# Drive_Module.net
KiCad netlist of a schematic drawn in Altium Designer
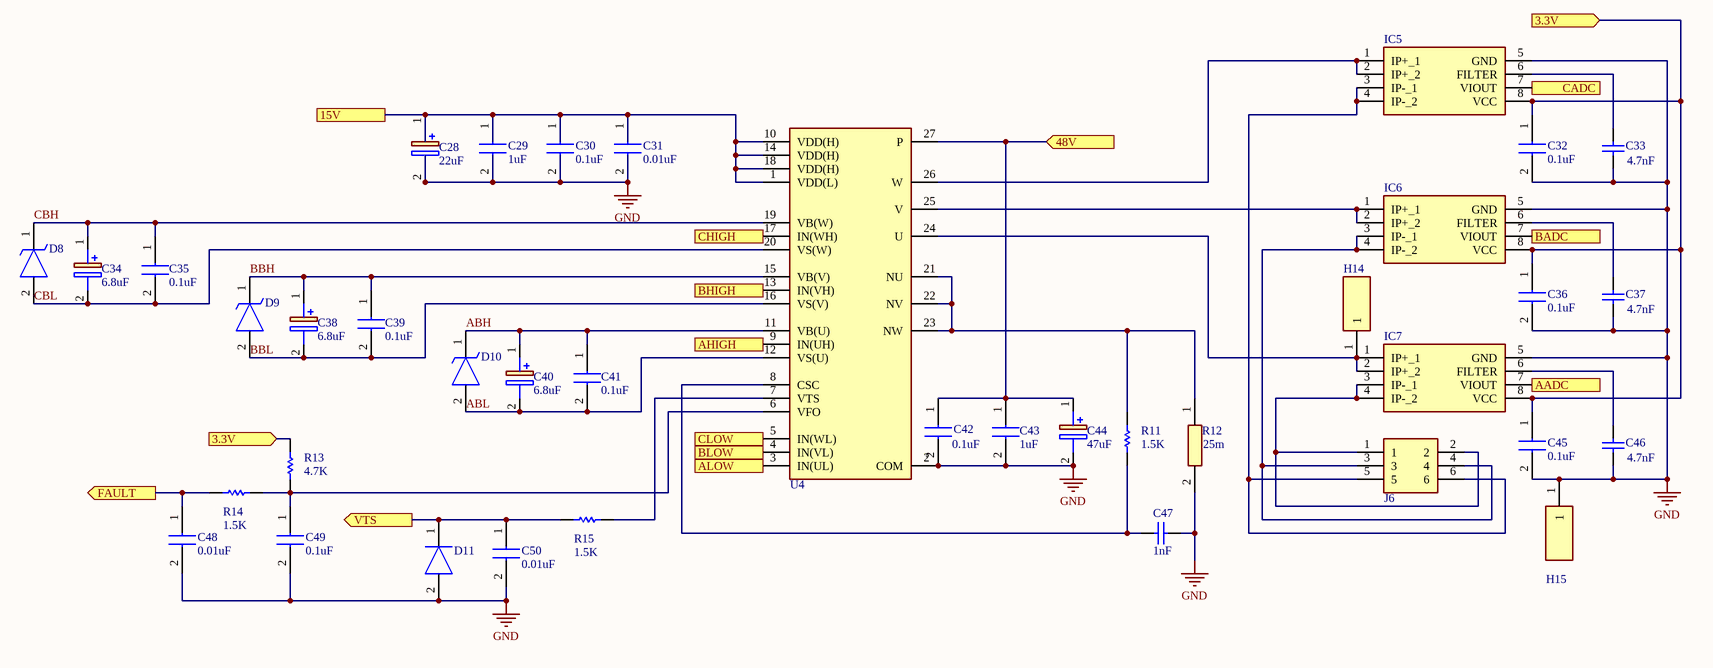
[diagram p0: Drive_Module.SchDoc]

(export (version "E")
  (design (tool "Eeschema 10.0.6"))
  (components
    (comp (ref "C28")
      (value "22uF")
      (footprint "CAPPRD200W50D550H1250")
      (description "Capacitor Polarised  25V")
      (fields
        (field (name "MANUFACTURER_PART_NUMBER") "UPW1E220MDD")
        (field (name "MOUSER PART NUMBER") "647-UPW1E220MDD")
      )
      (libsource (lib "ee_453_Schulz") (part "UPW1E220MDD"))
    )
    (comp (ref "C29")
      (value "1uF")
      (footprint "C330C105K5R5TA")
      (description "Capacitor 50V")
      (fields
        (field (name "MANUFACTURER_PART_NUMBER") "C330C105K5R5TA")
        (field (name "MOUSER PART NUMBER") "80-C330C105K5R")
      )
      (libsource (lib "ee_453_Schulz") (part "C330C105K5R5TA"))
    )
    (comp (ref "C30")
      (value "0.1uF")
      (footprint "K104K10X7RF5UH5")
      (description "Capacitor 50V")
      (fields
        (field (name "MANUFACTURER_PART_NUMBER") "K104K10X7RF5UH5")
        (field (name "MOUSER PART NUMBER") "594-K104K10X7RF5UH5")
      )
      (libsource (lib "ee_453_Schulz") (part "K104K10X7RF5UH5"))
    )
    (comp (ref "C31")
      (value "0.01uF")
      (footprint "C315C103K5R5TA7990")
      (description "Capacitor 50V")
      (fields (field (name "MANUFACTURER_PART_NUMBER") "C315C103K5R5TA7990"))
      (libsource (lib "ee_453_Schulz") (part "C315C103K5R5TA7990"))
    )
    (comp (ref "C32")
      (value "0.1uF")
      (footprint "CAPC1608X95N")
      (description "Capacitor 50V")
      (fields
        (field (name "MANUFACTURER_PART_NUMBER") "C0603C104K5RAC3121")
        (field (name "MOUSER PART NUMBER") "80-C603C104K5RAC3121")
      )
      (libsource (lib "ee_453_Schulz") (part "C0603C104K5RAC3121"))
    )
    (comp (ref "C33")
      (value "4.7nF")
      (footprint "CAPC1608X90X35ML10T15")
      (fields (field (name "PART NUMBER") "GRM188R71H472KA01D") (field (name "MANUFACTURER") "Murata"))
      (libsource (lib "Altium Content Vault") (part "CAP"))
    )
    (comp (ref "C34")
      (value "6.8uF")
      (footprint "CAPPRD150W45D425H1250")
      (description "Capacitor Polarised")
      (fields
        (field (name "MANUFACTURER_PART_NUMBER") "UPW1J6R8MDD6")
        (field (name "RS PART NUMBER") "8515424")
      )
      (libsource (lib "ee_453_Schulz") (part "UPW1J6R8MDD6"))
    )
    (comp (ref "C35")
      (value "0.1uF")
      (footprint "K104K10X7RF5UH5")
      (description "Capacitor 50V")
      (fields
        (field (name "MANUFACTURER_PART_NUMBER") "K104K10X7RF5UH5")
        (field (name "MOUSER PART NUMBER") "594-K104K10X7RF5UH5")
      )
      (libsource (lib "ee_453_Schulz") (part "K104K10X7RF5UH5"))
    )
    (comp (ref "C36")
      (value "0.1uF")
      (footprint "CAPC1608X95N")
      (description "Capacitor 50V")
      (fields
        (field (name "MANUFACTURER_PART_NUMBER") "C0603C104K5RAC3121")
        (field (name "MOUSER PART NUMBER") "80-C603C104K5RAC3121")
      )
      (libsource (lib "ee_453_Schulz") (part "C0603C104K5RAC3121"))
    )
    (comp (ref "C37")
      (value "4.7nF")
      (footprint "CAPC1608X90X35ML10T15")
      (fields (field (name "PART NUMBER") "GRM188R71H472KA01D") (field (name "MANUFACTURER") "Murata"))
      (libsource (lib "Altium Content Vault") (part "CAP"))
    )
    (comp (ref "C38")
      (value "6.8uF")
      (footprint "CAPPRD150W45D425H1250")
      (description "Capacitor Polarised")
      (fields
        (field (name "MANUFACTURER_PART_NUMBER") "UPW1J6R8MDD6")
        (field (name "RS PART NUMBER") "8515424")
      )
      (libsource (lib "ee_453_Schulz") (part "UPW1J6R8MDD6"))
    )
    (comp (ref "C39")
      (value "0.1uF")
      (footprint "K104K10X7RF5UH5")
      (description "Capacitor 50V")
      (fields
        (field (name "MANUFACTURER_PART_NUMBER") "K104K10X7RF5UH5")
        (field (name "MOUSER PART NUMBER") "594-K104K10X7RF5UH5")
      )
      (libsource (lib "ee_453_Schulz") (part "K104K10X7RF5UH5"))
    )
    (comp (ref "C40")
      (value "6.8uF")
      (footprint "CAPPRD150W45D425H1250")
      (description "UPW1J6R8MDD6")
      (fields (field (name "RS PART NUMBER") "8515424"))
      (libsource (lib "ee_453_Schulz") (part "UPW1J6R8MDD6"))
    )
    (comp (ref "C41")
      (value "0.1uF")
      (footprint "K104K10X7RF5UH5")
      (description "Capacitor 50V")
      (fields
        (field (name "MANUFACTURER_PART_NUMBER") "K104K10X7RF5UH5")
        (field (name "MOUSER PART NUMBER") "594-K104K10X7RF5UH5")
      )
      (libsource (lib "ee_453_Schulz") (part "K104K10X7RF5UH5"))
    )
    (comp (ref "C42")
      (value "0.1uF")
      (footprint "CAPC1608X90N")
      (description "Capacitor")
      (fields
        (field (name "MANUFACTURER_PART_NUMBER") "GRM188R72A104MA35D")
        (field (name "MOUSER PART NUMBER") "81-GRM188R72A104MA5D")
      )
      (libsource (lib "ee_453_Schulz") (part "GRM188R72A104MA35D"))
    )
    (comp (ref "C43")
      (value "1uF")
      (footprint "RCE5C1H104J2A2H03B")
      (description "Capacitor")
      (fields
        (field (name "MANUFACTURER_PART_NUMBER") "RDER72A105K2M1H03A")
        (field (name "MOUSER PART NUMBER") "81-RDER72A105K2M1H3A")
      )
      (libsource (lib "ee_453_Schulz") (part "RDER72A105K2M1H03A"))
    )
    (comp (ref "C44")
      (value "47uF")
      (footprint "CAPPRD350W65D800H1650")
      (description "Capacitor Polarised")
      (fields
        (field (name "MANUFACTURER_PART_NUMBER") "EEU-FS2A470")
        (field (name "MOUSER PART NUMBER") "667-EEU-FS2A470")
      )
      (libsource (lib "ee_453_Schulz") (part "EEU-FS2A470"))
    )
    (comp (ref "C45")
      (value "0.1uF")
      (footprint "CAPC1608X95N")
      (description "Capacitor 50V")
      (fields
        (field (name "MANUFACTURER_PART_NUMBER") "C0603C104K5RAC3121")
        (field (name "MOUSER PART NUMBER") "80-C603C104K5RAC3121")
      )
      (libsource (lib "ee_453_Schulz") (part "C0603C104K5RAC3121"))
    )
    (comp (ref "C46")
      (value "4.7nF")
      (footprint "CAPC1608X90X35ML10T15")
      (fields (field (name "PART NUMBER") "GRM188R71H472KA01D") (field (name "MANUFACTURER") "Murata"))
      (libsource (lib "Altium Content Vault") (part "CAP"))
    )
    (comp (ref "C47")
      (value "1nF")
      (footprint "CAPC2013X95X45NL10T25")
      (description "GRM2195C2A102JA01D")
      (fields (field (name "MANUFACTURER") "Murata"))
      (libsource (lib "Altium Content Vault") (part "CAP"))
    )
    (comp (ref "C48")
      (value "0.01uF")
      (footprint "C315C103K5R5TA7990")
      (description "Capacitor 50V")
      (fields (field (name "MANUFACTURER_PART_NUMBER") "C315C103K5R5TA7990"))
      (libsource (lib "ee_453_Schulz") (part "C315C103K5R5TA7990"))
    )
    (comp (ref "C49")
      (value "0.1uF")
      (footprint "K104K10X7RF5UH5")
      (description "Capacitor 50V")
      (fields
        (field (name "MANUFACTURER_PART_NUMBER") "K104K10X7RF5UH5")
        (field (name "MOUSER PART NUMBER") "594-K104K10X7RF5UH5")
      )
      (libsource (lib "ee_453_Schulz") (part "K104K10X7RF5UH5"))
    )
    (comp (ref "C50")
      (value "0.01uF")
      (footprint "C315C103K5R5TA7990")
      (description "Capacitor 50V")
      (fields (field (name "MANUFACTURER_PART_NUMBER") "C315C103K5R5TA7990"))
      (libsource (lib "ee_453_Schulz") (part "C315C103K5R5TA7990"))
    )
    (comp (ref "D8")
      (value "P6KE91A-E3_54")
      (footprint "DIOAD1910W86L670D310")
      (description "TVS Diode (Uni-directional)")
      (fields (field (name "MANUFACTURER_PART_NUMBER") "P6KE91A-E3/54"))
      (libsource (lib "ee_453_Schulz") (part "P6KE91A-E3_54"))
    )
    (comp (ref "D9")
      (value "P6KE91A-E3_54")
      (footprint "DIOAD1910W86L670D310")
      (description "TVS Diode (Uni-directional)")
      (fields (field (name "MANUFACTURER_PART_NUMBER") "P6KE91A-E3/54"))
      (libsource (lib "ee_453_Schulz") (part "P6KE91A-E3_54"))
    )
    (comp (ref "D10")
      (value "P6KE91A-E3_54")
      (footprint "DIOAD1910W86L670D310")
      (description "TVS Diode (Uni-directional)")
      (fields (field (name "MANUFACTURER_PART_NUMBER") "P6KE91A-E3/54"))
      (libsource (lib "ee_453_Schulz") (part "P6KE91A-E3_54"))
    )
    (comp (ref "D11")
      (value "BZX584C3V3-G3-08")
      (footprint "SODFL1608X75N")
      (description "Diode")
      (fields (field (name "MOUSER PART NUMBER") "78-BZX584C3V3-G3-08"))
      (libsource (lib "*") (part "BZX584C3V3-G3-08"))
    )
    (comp (ref "H14")
      (value "5003")
      (footprint "5003")
      (description "Hardware")
      (fields (field (name "MOUSER PART NUMBER") "534-5003"))
      (libsource (lib "ee_453_Schulz") (part "5003"))
    )
    (comp (ref "H15")
      (value "5003")
      (footprint "5003")
      (description "Hardware")
      (fields (field (name "MOUSER PART NUMBER") "534-5003"))
      (libsource (lib "") (part "5003_1"))
    )
    (comp (ref "IC5")
      (value "ACS725LLCTR-20AB-T")
      (footprint "SOT127P600X175-8N")
      (description "Integrated Circuit")
      (libsource (lib "ee_453_Schulz") (part "ACS725LLCTR-20AB-T"))
    )
    (comp (ref "IC6")
      (value "ACS725LLCTR-20AB-T")
      (footprint "SOT127P600X175-8N")
      (description "Integrated Circuit")
      (libsource (lib "ee_453_Schulz") (part "ACS725LLCTR-20AB-T"))
    )
    (comp (ref "IC7")
      (value "ACS725LLCTR-20AB-T")
      (footprint "SOT127P600X175-8N")
      (description "Integrated Circuit")
      (libsource (lib "ee_453_Schulz") (part "ACS725LLCTR-20AB-T"))
    )
    (comp (ref "J6")
      (value "1730515")
      (footprint "1730515")
      (description "Connector")
      (fields (field (name "MOUSER PART NUMBER") "651-1730515"))
      (libsource (lib "ee_453_Schulz") (part "1730515"))
    )
    (comp (ref "R11")
      (value "1.5K")
      (footprint "AXIAL-0.3")
      (description "Resistor")
      (fields (field (name "Comment") "Res1") (field (name "PUBLISHER") "Altium Limited"))
      (libsource (lib "Miscellaneous Devices") (part "Res1"))
    )
    (comp (ref "R12")
      (value "25m")
      (footprint "RESC7146X175N")
      (description "Resistor")
      (fields
        (field (name "MANUFACTURER_PART_NUMBER") "WSHP2818R0500FEA")
        (field (name "MOUSER PART NUMBER") "71-WSHP2818R0500FEA")
      )
      (libsource (lib "ee_453_Schulz") (part "WSHP2818R0500FEA"))
    )
    (comp (ref "R13")
      (value "4.7K")
      (footprint "AXIAL-0.3")
      (description "Resistor")
      (fields (field (name "Comment") "Res1") (field (name "PUBLISHER") "Altium Limited"))
      (libsource (lib "Miscellaneous Devices") (part "Res1"))
    )
    (comp (ref "R14")
      (value "1.5K")
      (footprint "AXIAL-0.3")
      (description "Resistor")
      (fields (field (name "Comment") "Res1") (field (name "PUBLISHER") "Altium Limited"))
      (libsource (lib "Miscellaneous Devices") (part "Res1"))
    )
    (comp (ref "R15")
      (value "1.5K")
      (footprint "AXIAL-0.3")
      (description "Resistor")
      (fields (field (name "Comment") "Res1") (field (name "PUBLISHER") "Altium Limited"))
      (libsource (lib "Miscellaneous Devices") (part "Res1"))
    )
    (comp (ref "U4")
      (value "FNB34060T")
      (footprint "FNB34060T:FNB34060T")
      (libsource (lib "ee_453_Schulz") (part "FNB34060T"))
    )
  )
  (nets
    (net (code "1") (name "/3.3V") (class "Default")
      (node (ref "C32") (pin "1") (pinfunction "1_1") (pintype "passive"))
      (node (ref "C36") (pin "1") (pinfunction "1_1") (pintype "passive"))
      (node (ref "C45") (pin "1") (pinfunction "1_1") (pintype "passive"))
      (node (ref "IC5") (pin "8") (pinfunction "VCC_8") (pintype "passive"))
      (node (ref "IC6") (pin "8") (pinfunction "VCC_8") (pintype "passive"))
      (node (ref "IC7") (pin "8") (pinfunction "VCC_8") (pintype "passive"))
      (node (ref "R13") (pin "2") (pinfunction "2_2") (pintype "passive"))
    )
    (net (code "2") (name "/15V") (class "Default")
      (node (ref "C28") (pin "1") (pinfunction "+_1") (pintype "passive"))
      (node (ref "C29") (pin "1") (pinfunction "1_1") (pintype "passive"))
      (node (ref "C30") (pin "1") (pinfunction "1_1") (pintype "passive"))
      (node (ref "C31") (pin "1") (pinfunction "1_1") (pintype "passive"))
      (node (ref "U4") (pin "1") (pinfunction "VDD(L)_1") (pintype "power_in"))
      (node (ref "U4") (pin "10") (pinfunction "VDD(H)_10") (pintype "power_in"))
      (node (ref "U4") (pin "14") (pinfunction "VDD(H)_14") (pintype "power_in"))
      (node (ref "U4") (pin "18") (pinfunction "VDD(H)_18") (pintype "power_in"))
    )
    (net (code "3") (name "/48V") (class "Default")
      (node (ref "C42") (pin "1") (pinfunction "1_1") (pintype "passive"))
      (node (ref "C43") (pin "1") (pinfunction "1_1") (pintype "passive"))
      (node (ref "C44") (pin "1") (pinfunction "+_1") (pintype "passive"))
      (node (ref "U4") (pin "27") (pinfunction "P_27") (pintype "passive"))
    )
    (net (code "4") (name "/AADC") (class "Default")
      (node (ref "IC7") (pin "7") (pinfunction "VIOUT_7") (pintype "passive"))
    )
    (net (code "5") (name "/ABH") (class "Default")
      (node (ref "C40") (pin "1") (pinfunction "+_1") (pintype "passive"))
      (node (ref "C41") (pin "1") (pinfunction "1_1") (pintype "passive"))
      (node (ref "D10") (pin "1") (pinfunction "K_1") (pintype "passive"))
      (node (ref "U4") (pin "11") (pinfunction "VB(U)_11") (pintype "power_in"))
    )
    (net (code "6") (name "/ABL") (class "Default")
      (node (ref "C40") (pin "2") (pinfunction "-_2") (pintype "passive"))
      (node (ref "C41") (pin "2") (pinfunction "2_2") (pintype "passive"))
      (node (ref "D10") (pin "2") (pinfunction "A_2") (pintype "passive"))
      (node (ref "U4") (pin "12") (pinfunction "VS(U)_12") (pintype "power_in"))
    )
    (net (code "7") (name "/AHIGH") (class "Default")
      (node (ref "U4") (pin "9") (pinfunction "IN(UH)_9") (pintype "passive"))
    )
    (net (code "8") (name "/ALOW") (class "Default")
      (node (ref "U4") (pin "3") (pinfunction "IN(UL)_3") (pintype "passive"))
    )
    (net (code "9") (name "/BADC") (class "Default")
      (node (ref "IC6") (pin "7") (pinfunction "VIOUT_7") (pintype "passive"))
    )
    (net (code "10") (name "/BBH") (class "Default")
      (node (ref "C38") (pin "1") (pinfunction "+_1") (pintype "passive"))
      (node (ref "C39") (pin "1") (pinfunction "1_1") (pintype "passive"))
      (node (ref "D9") (pin "1") (pinfunction "K_1") (pintype "passive"))
      (node (ref "U4") (pin "15") (pinfunction "VB(V)_15") (pintype "power_in"))
    )
    (net (code "11") (name "/BBL") (class "Default")
      (node (ref "C38") (pin "2") (pinfunction "-_2") (pintype "passive"))
      (node (ref "C39") (pin "2") (pinfunction "2_2") (pintype "passive"))
      (node (ref "D9") (pin "2") (pinfunction "A_2") (pintype "passive"))
      (node (ref "U4") (pin "16") (pinfunction "VS(V)_16") (pintype "power_in"))
    )
    (net (code "12") (name "/BHIGH") (class "Default")
      (node (ref "U4") (pin "13") (pinfunction "IN(VH)_13") (pintype "passive"))
    )
    (net (code "13") (name "/BLOW") (class "Default")
      (node (ref "U4") (pin "4") (pinfunction "IN(VL)_4") (pintype "passive"))
    )
    (net (code "14") (name "/CADC") (class "Default")
      (node (ref "IC5") (pin "7") (pinfunction "VIOUT_7") (pintype "passive"))
    )
    (net (code "15") (name "/CBH") (class "Default")
      (node (ref "C34") (pin "1") (pinfunction "+_1") (pintype "passive"))
      (node (ref "C35") (pin "1") (pinfunction "1_1") (pintype "passive"))
      (node (ref "D8") (pin "1") (pinfunction "K_1") (pintype "passive"))
      (node (ref "U4") (pin "19") (pinfunction "VB(W)_19") (pintype "power_in"))
    )
    (net (code "16") (name "/CBL") (class "Default")
      (node (ref "C34") (pin "2") (pinfunction "-_2") (pintype "passive"))
      (node (ref "C35") (pin "2") (pinfunction "2_2") (pintype "passive"))
      (node (ref "D8") (pin "2") (pinfunction "A_2") (pintype "passive"))
      (node (ref "U4") (pin "20") (pinfunction "VS(W)_20") (pintype "power_in"))
    )
    (net (code "17") (name "/CHIGH") (class "Default")
      (node (ref "U4") (pin "17") (pinfunction "IN(WH)_17") (pintype "passive"))
    )
    (net (code "18") (name "/CLOW") (class "Default")
      (node (ref "U4") (pin "5") (pinfunction "IN(WL)_5") (pintype "passive"))
    )
    (net (code "19") (name "/FAULT") (class "Default")
      (node (ref "C48") (pin "1") (pinfunction "1_1") (pintype "passive"))
      (node (ref "R14") (pin "1") (pinfunction "1_1") (pintype "passive"))
    )
    (net (code "20") (name "/VTS") (class "Default")
      (node (ref "C50") (pin "1") (pinfunction "1_1") (pintype "passive"))
      (node (ref "D11") (pin "1") (pinfunction "K_1") (pintype "passive"))
      (node (ref "R15") (pin "2") (pinfunction "2_2") (pintype "passive"))
    )
    (net (code "21") (name "GND") (class "Default")
      (node (ref "C28") (pin "2") (pinfunction "-_2") (pintype "passive"))
      (node (ref "C29") (pin "2") (pinfunction "2_2") (pintype "passive"))
      (node (ref "C30") (pin "2") (pinfunction "2_2") (pintype "passive"))
      (node (ref "C31") (pin "2") (pinfunction "2_2") (pintype "passive"))
      (node (ref "C32") (pin "2") (pinfunction "2_2") (pintype "passive"))
      (node (ref "C33") (pin "2") (pinfunction "2_2") (pintype "passive"))
      (node (ref "C36") (pin "2") (pinfunction "2_2") (pintype "passive"))
      (node (ref "C37") (pin "2") (pinfunction "2_2") (pintype "passive"))
      (node (ref "C42") (pin "2") (pinfunction "2_2") (pintype "passive"))
      (node (ref "C43") (pin "2") (pinfunction "2_2") (pintype "passive"))
      (node (ref "C44") (pin "2") (pinfunction "-_2") (pintype "passive"))
      (node (ref "C45") (pin "2") (pinfunction "2_2") (pintype "passive"))
      (node (ref "C46") (pin "2") (pinfunction "2_2") (pintype "passive"))
      (node (ref "C47") (pin "2") (pinfunction "2_2") (pintype "passive"))
      (node (ref "C48") (pin "2") (pinfunction "2_2") (pintype "passive"))
      (node (ref "C49") (pin "2") (pinfunction "2_2") (pintype "passive"))
      (node (ref "C50") (pin "2") (pinfunction "2_2") (pintype "passive"))
      (node (ref "D11") (pin "2") (pinfunction "A_2") (pintype "passive"))
      (node (ref "H15") (pin "1") (pinfunction "1_1") (pintype "passive"))
      (node (ref "IC5") (pin "5") (pinfunction "GND_5") (pintype "passive"))
      (node (ref "IC6") (pin "5") (pinfunction "GND_5") (pintype "passive"))
      (node (ref "IC7") (pin "5") (pinfunction "GND_5") (pintype "passive"))
      (node (ref "R12") (pin "2") (pinfunction "2_2") (pintype "passive"))
      (node (ref "U4") (pin "2") (pinfunction "COM_2") (pintype "power_in"))
    )
    (net (code "22") (name "Net-(IC5-FILTER)") (class "Default")
      (node (ref "C33") (pin "1") (pinfunction "1_1") (pintype "passive"))
      (node (ref "IC5") (pin "6") (pinfunction "FILTER_6") (pintype "passive"))
    )
    (net (code "23") (name "Net-(IC5-IP+_1)") (class "Default")
      (node (ref "IC5") (pin "1") (pinfunction "IP+_1_1") (pintype "passive"))
      (node (ref "IC5") (pin "2") (pinfunction "IP+_2_2") (pintype "passive"))
      (node (ref "U4") (pin "26") (pinfunction "W_26") (pintype "passive"))
    )
    (net (code "24") (name "Net-(IC5-IP-_1)") (class "Default")
      (node (ref "IC5") (pin "3") (pinfunction "IP-_1_3") (pintype "passive"))
      (node (ref "IC5") (pin "4") (pinfunction "IP-_2_4") (pintype "passive"))
      (node (ref "J6") (pin "5") (pinfunction "5_5") (pintype "passive"))
      (node (ref "J6") (pin "6") (pinfunction "6_6") (pintype "passive"))
    )
    (net (code "25") (name "Net-(IC6-FILTER)") (class "Default")
      (node (ref "C37") (pin "1") (pinfunction "1_1") (pintype "passive"))
      (node (ref "IC6") (pin "6") (pinfunction "FILTER_6") (pintype "passive"))
    )
    (net (code "26") (name "Net-(IC6-IP+_1)") (class "Default")
      (node (ref "IC6") (pin "1") (pinfunction "IP+_1_1") (pintype "passive"))
      (node (ref "IC6") (pin "2") (pinfunction "IP+_2_2") (pintype "passive"))
      (node (ref "U4") (pin "25") (pinfunction "V_25") (pintype "passive"))
    )
    (net (code "27") (name "Net-(IC6-IP-_1)") (class "Default")
      (node (ref "IC6") (pin "3") (pinfunction "IP-_1_3") (pintype "passive"))
      (node (ref "IC6") (pin "4") (pinfunction "IP-_2_4") (pintype "passive"))
      (node (ref "J6") (pin "3") (pinfunction "3_3") (pintype "passive"))
      (node (ref "J6") (pin "4") (pinfunction "4_4") (pintype "passive"))
    )
    (net (code "28") (name "Net-(IC7-FILTER)") (class "Default")
      (node (ref "C46") (pin "1") (pinfunction "1_1") (pintype "passive"))
      (node (ref "IC7") (pin "6") (pinfunction "FILTER_6") (pintype "passive"))
    )
    (net (code "29") (name "Net-(IC7-IP+_1)") (class "Default")
      (node (ref "H14") (pin "1") (pinfunction "1_1") (pintype "passive"))
      (node (ref "IC7") (pin "1") (pinfunction "IP+_1_1") (pintype "passive"))
      (node (ref "IC7") (pin "2") (pinfunction "IP+_2_2") (pintype "passive"))
      (node (ref "U4") (pin "24") (pinfunction "U_24") (pintype "passive"))
    )
    (net (code "30") (name "Net-(IC7-IP-_1)") (class "Default")
      (node (ref "IC7") (pin "3") (pinfunction "IP-_1_3") (pintype "passive"))
      (node (ref "IC7") (pin "4") (pinfunction "IP-_2_4") (pintype "passive"))
      (node (ref "J6") (pin "1") (pinfunction "1_1") (pintype "passive"))
      (node (ref "J6") (pin "2") (pinfunction "2_2") (pintype "passive"))
    )
    (net (code "31") (name "Net-(U4-CSC)") (class "Default")
      (node (ref "C47") (pin "1") (pinfunction "1_1") (pintype "passive"))
      (node (ref "R11") (pin "1") (pinfunction "1_1") (pintype "passive"))
      (node (ref "U4") (pin "8") (pinfunction "CSC_8") (pintype "passive"))
    )
    (net (code "32") (name "Net-(U4-NU)") (class "Default")
      (node (ref "R11") (pin "2") (pinfunction "2_2") (pintype "passive"))
      (node (ref "R12") (pin "1") (pinfunction "1_1") (pintype "passive"))
      (node (ref "U4") (pin "21") (pinfunction "NU_21") (pintype "passive"))
      (node (ref "U4") (pin "22") (pinfunction "NV_22") (pintype "passive"))
      (node (ref "U4") (pin "23") (pinfunction "NW_23") (pintype "passive"))
    )
    (net (code "33") (name "Net-(U4-VFO)") (class "Default")
      (node (ref "C49") (pin "1") (pinfunction "1_1") (pintype "passive"))
      (node (ref "R13") (pin "1") (pinfunction "1_1") (pintype "passive"))
      (node (ref "R14") (pin "2") (pinfunction "2_2") (pintype "passive"))
      (node (ref "U4") (pin "6") (pinfunction "VFO_6") (pintype "passive"))
    )
    (net (code "34") (name "Net-(U4-VTS)") (class "Default")
      (node (ref "R15") (pin "1") (pinfunction "1_1") (pintype "passive"))
      (node (ref "U4") (pin "7") (pinfunction "VTS_7") (pintype "passive"))
    )
  )
)
